# RS232.net
KiCad netlist of a schematic drawn in Altium Designer
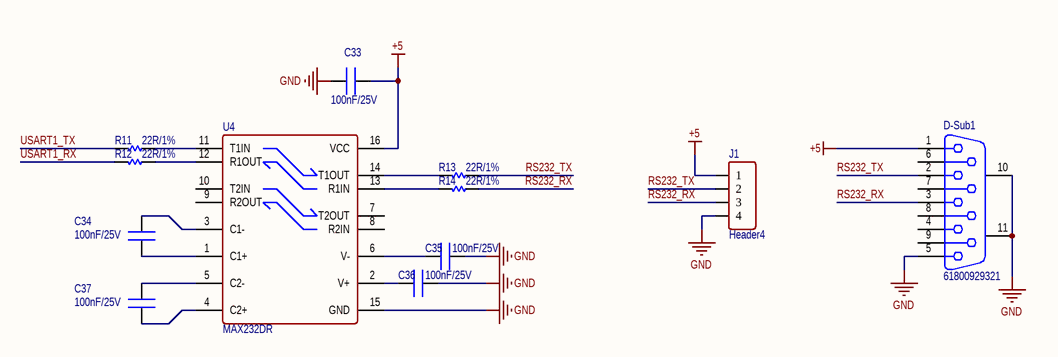
[diagram p0: RS232.SchDoc]

(export (version "E")
  (design (tool "Eeschema 10.0.6"))
  (components
    (comp (ref "C33")
      (value "100nF/25V")
      (footprint "CN-SMD-0603")
      (description "CL10B104KA8NNNC")
      (libsource (lib "Library") (part "CN"))
    )
    (comp (ref "C34")
      (value "100nF/25V")
      (footprint "CN-SMD-0603")
      (description "CL10B104KA8NNNC")
      (libsource (lib "Library") (part "CN"))
    )
    (comp (ref "C35")
      (value "100nF/25V")
      (footprint "CN-SMD-0603")
      (description "CL10B104KA8NNNC")
      (libsource (lib "Library") (part "CN"))
    )
    (comp (ref "C36")
      (value "100nF/25V")
      (footprint "CN-SMD-0603")
      (description "CL10B104KA8NNNC")
      (libsource (lib "Library") (part "CN"))
    )
    (comp (ref "C37")
      (value "100nF/25V")
      (footprint "CN-SMD-0603")
      (description "CL10B104KA8NNNC")
      (libsource (lib "Library") (part "CN"))
    )
    (comp (ref "D-Sub1")
      (value "61800929321")
      (footprint "COM9E")
      (fields
        (field (name "MANUFACTURER") "Würth Elektronik eiSos GmbH")
        (field (name "CREATED BY") "Christin Zierenner")
      )
      (libsource (lib "Library") (part "CON 9BD"))
    )
    (comp (ref "J1")
      (value "Header4")
      (footprint "XH2.54-4-DIP")
      (description "Connector 4")
      (fields
        (field (name "MANUFACTURER") "Würth Elektronik eiSos GmbH")
        (field (name "PARTNO") "613002143121")
        (field (name "CREATED BY") "Karrer Zheng")
      )
      (libsource (lib "Library") (part "Header4"))
    )
    (comp (ref "R11")
      (value "22R/1%")
      (footprint "RES-SMD-0603")
      (description "ERJ-3EKF22R0V")
      (libsource (lib "Library") (part "Res-SMD"))
    )
    (comp (ref "R12")
      (value "22R/1%")
      (footprint "RES-SMD-0603")
      (description "ERJ-3EKF22R0V")
      (libsource (lib "Library") (part "Res-SMD"))
    )
    (comp (ref "R13")
      (value "22R/1%")
      (footprint "RES-SMD-0603")
      (description "ERJ-3EKF22R0V")
      (libsource (lib "Library") (part "Res-SMD"))
    )
    (comp (ref "R14")
      (value "22R/1%")
      (footprint "RES-SMD-0603")
      (description "ERJ-3EKF22R0V")
      (libsource (lib "Library") (part "Res-SMD"))
    )
    (comp (ref "U4") (value "MAX232DR") (footprint "SO16") (libsource (lib "Library") (part "MAX3232")))
  )
  (nets
    (net (code "1") (name "+5") (class "Default")
      (node (ref "C33") (pin "1") (pinfunction "1_1") (pintype "passive"))
      (node (ref "D-Sub1") (pin "1") (pinfunction "1_1") (pintype "passive"))
      (node (ref "J1") (pin "1") (pinfunction "1_1") (pintype "passive"))
      (node (ref "U4") (pin "16") (pinfunction "VCC_16") (pintype "power_in"))
    )
    (net (code "2") (name "/RS232_RX") (class "Default")
      (node (ref "D-Sub1") (pin "3") (pinfunction "3_3") (pintype "passive"))
      (node (ref "J1") (pin "3") (pinfunction "3_3") (pintype "passive"))
      (node (ref "R14") (pin "1") (pinfunction "1_1") (pintype "passive"))
    )
    (net (code "3") (name "/RS232_TX") (class "Default")
      (node (ref "D-Sub1") (pin "2") (pinfunction "2_2") (pintype "passive"))
      (node (ref "J1") (pin "2") (pinfunction "2_2") (pintype "passive"))
      (node (ref "R13") (pin "1") (pinfunction "1_1") (pintype "passive"))
    )
    (net (code "4") (name "/USART1_RX") (class "Default")
      (node (ref "R12") (pin "2") (pinfunction "2_2") (pintype "passive"))
    )
    (net (code "5") (name "/USART1_TX") (class "Default")
      (node (ref "R11") (pin "2") (pinfunction "2_2") (pintype "passive"))
    )
    (net (code "6") (name "GND") (class "Default")
      (node (ref "C33") (pin "2") (pinfunction "2_2") (pintype "passive"))
      (node (ref "C35") (pin "1") (pinfunction "1_1") (pintype "passive"))
      (node (ref "C36") (pin "1") (pinfunction "1_1") (pintype "passive"))
      (node (ref "D-Sub1") (pin "10") (pinfunction "MH1_10") (pintype "passive"))
      (node (ref "D-Sub1") (pin "11") (pinfunction "MH2_11") (pintype "passive"))
      (node (ref "D-Sub1") (pin "5") (pinfunction "5_5") (pintype "passive"))
      (node (ref "J1") (pin "4") (pinfunction "4_4") (pintype "passive"))
      (node (ref "U4") (pin "15") (pinfunction "GND_15") (pintype "power_in"))
    )
    (net (code "7") (name "Net-(U4-C1+)") (class "Default")
      (node (ref "C34") (pin "1") (pinfunction "1_1") (pintype "passive"))
      (node (ref "U4") (pin "1") (pinfunction "C1+_1") (pintype "power_in"))
    )
    (net (code "8") (name "Net-(U4-C1-)") (class "Default")
      (node (ref "C34") (pin "2") (pinfunction "2_2") (pintype "passive"))
      (node (ref "U4") (pin "3") (pinfunction "C1-_3") (pintype "passive"))
    )
    (net (code "9") (name "Net-(U4-C2+)") (class "Default")
      (node (ref "C37") (pin "1") (pinfunction "1_1") (pintype "passive"))
      (node (ref "U4") (pin "4") (pinfunction "C2+_4") (pintype "passive"))
    )
    (net (code "10") (name "Net-(U4-C2-)") (class "Default")
      (node (ref "C37") (pin "2") (pinfunction "2_2") (pintype "passive"))
      (node (ref "U4") (pin "5") (pinfunction "C2-_5") (pintype "power_in"))
    )
    (net (code "11") (name "Net-(U4-R1IN)") (class "Default")
      (node (ref "R14") (pin "2") (pinfunction "2_2") (pintype "passive"))
      (node (ref "U4") (pin "13") (pinfunction "R1IN_13") (pintype "passive"))
    )
    (net (code "12") (name "Net-(U4-R1OUT)") (class "Default")
      (node (ref "R12") (pin "1") (pinfunction "1_1") (pintype "passive"))
      (node (ref "U4") (pin "12") (pinfunction "R1OUT_12") (pintype "passive"))
    )
    (net (code "13") (name "Net-(U4-T1IN)") (class "Default")
      (node (ref "R11") (pin "1") (pinfunction "1_1") (pintype "passive"))
      (node (ref "U4") (pin "11") (pinfunction "T1IN_11") (pintype "passive"))
    )
    (net (code "14") (name "Net-(U4-T1OUT)") (class "Default")
      (node (ref "R13") (pin "2") (pinfunction "2_2") (pintype "passive"))
      (node (ref "U4") (pin "14") (pinfunction "T1OUT_14") (pintype "power_in"))
    )
    (net (code "15") (name "Net-(U4-V+)") (class "Default")
      (node (ref "C36") (pin "2") (pinfunction "2_2") (pintype "passive"))
      (node (ref "U4") (pin "2") (pinfunction "V+_2") (pintype "passive"))
    )
    (net (code "16") (name "Net-(U4-V-)") (class "Default")
      (node (ref "C35") (pin "2") (pinfunction "2_2") (pintype "passive"))
      (node (ref "U4") (pin "6") (pinfunction "V-_6") (pintype "passive"))
    )
    (net (code "17") (name "unconnected-(D-Sub1-Pad4)") (class "Default")
      (node (ref "D-Sub1") (pin "4") (pinfunction "4_4") (pintype "passive"))
    )
    (net (code "18") (name "unconnected-(D-Sub1-Pad6)") (class "Default")
      (node (ref "D-Sub1") (pin "6") (pinfunction "6_6") (pintype "passive"))
    )
    (net (code "19") (name "unconnected-(D-Sub1-Pad7)") (class "Default")
      (node (ref "D-Sub1") (pin "7") (pinfunction "7_7") (pintype "passive"))
    )
    (net (code "20") (name "unconnected-(D-Sub1-Pad8)") (class "Default")
      (node (ref "D-Sub1") (pin "8") (pinfunction "8_8") (pintype "passive"))
    )
    (net (code "21") (name "unconnected-(D-Sub1-Pad9)") (class "Default")
      (node (ref "D-Sub1") (pin "9") (pinfunction "9_9") (pintype "passive"))
    )
    (net (code "22") (name "unconnected-(U4-R2IN-Pad8)") (class "Default")
      (node (ref "U4") (pin "8") (pinfunction "R2IN_8") (pintype "passive"))
    )
    (net (code "23") (name "unconnected-(U4-R2OUT-Pad9)") (class "Default")
      (node (ref "U4") (pin "9") (pinfunction "R2OUT_9") (pintype "passive"))
    )
    (net (code "24") (name "unconnected-(U4-T2IN-Pad10)") (class "Default")
      (node (ref "U4") (pin "10") (pinfunction "T2IN_10") (pintype "passive"))
    )
    (net (code "25") (name "unconnected-(U4-T2OUT-Pad7)") (class "Default")
      (node (ref "U4") (pin "7") (pinfunction "T2OUT_7") (pintype "passive"))
    )
  )
)
